# Power_Board_V1.net
KiCad netlist of a schematic drawn in EAGLE
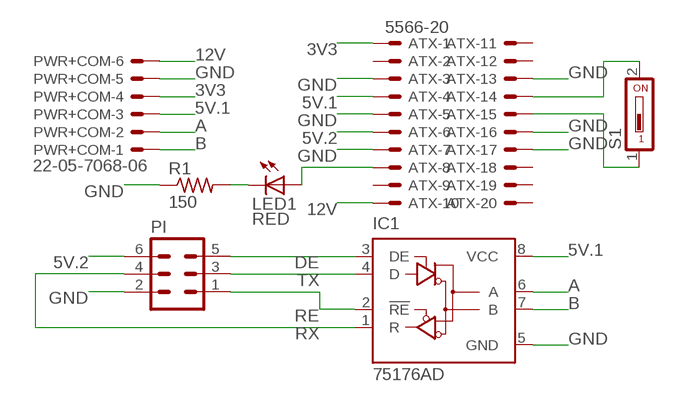
[diagram p0: schematic, sheet 1]

(export (version "E")
  (design (tool "Eeschema 10.0.6"))
  (components
    (comp (ref "ATX")
      (value "5566-20")
      (footprint "eagle-import:5566-20")
      (libsource (lib "eagle-import") (part "5566-20"))
    )
    (comp (ref "IC1")
      (value "75176AD")
      (footprint "eagle-import:D_R-PDSO-G8")
      (libsource (lib "eagle-import") (part "75176AD"))
    )
    (comp (ref "LED1")
      (value "RED")
      (footprint "eagle-import:CHIPLED_1206")
      (libsource (lib "eagle-import") (part "LEDCHIPLED_1206"))
    )
    (comp (ref "PI")
      (value "MA03-2")
      (footprint "eagle-import:MA03-2")
      (libsource (lib "eagle-import") (part "MA03-2"))
    )
    (comp (ref "PWR+COM")
      (value "22-05-7068-06")
      (footprint "eagle-import:7395-06")
      (libsource (lib "eagle-import") (part "22-?-0605-7068"))
    )
    (comp (ref "R1")
      (value "150")
      (footprint "eagle-import:R0805")
      (libsource (lib "eagle-import") (part "R-US_R0805"))
    )
    (comp (ref "S1")
      (value "SD4-01")
      (footprint "eagle-import:SD4-01")
      (libsource (lib "eagle-import") (part "SD4-01"))
    )
  )
  (nets
    (net (code "1") (name "/3V3") (class "Default")
      (node (ref "ATX") (pin "1") (pinfunction "S_1") (pintype "passive"))
      (node (ref "PWR+COM") (pin "4") (pinfunction "S_4") (pintype "passive"))
    )
    (net (code "2") (name "/5V.1") (class "Default")
      (node (ref "ATX") (pin "4") (pinfunction "S_4") (pintype "passive"))
      (node (ref "IC1") (pin "8") (pinfunction "VCC_8") (pintype "power_in"))
      (node (ref "PWR+COM") (pin "3") (pinfunction "S_3") (pintype "passive"))
    )
    (net (code "3") (name "/5V.2") (class "Default")
      (node (ref "ATX") (pin "6") (pinfunction "S_6") (pintype "passive"))
      (node (ref "PI") (pin "6") (pinfunction "6_6") (pintype "passive"))
    )
    (net (code "4") (name "/12V") (class "Default")
      (node (ref "ATX") (pin "10") (pinfunction "S_10") (pintype "passive"))
      (node (ref "PWR+COM") (pin "6") (pinfunction "S_6") (pintype "passive"))
    )
    (net (code "5") (name "/A") (class "Default")
      (node (ref "IC1") (pin "6") (pinfunction "A_6") (pintype "output"))
      (node (ref "PWR+COM") (pin "2") (pinfunction "S_2") (pintype "passive"))
    )
    (net (code "6") (name "/B") (class "Default")
      (node (ref "IC1") (pin "7") (pinfunction "B_7") (pintype "output"))
      (node (ref "PWR+COM") (pin "1") (pinfunction "S_1") (pintype "passive"))
    )
    (net (code "7") (name "/DE") (class "Default")
      (node (ref "IC1") (pin "3") (pinfunction "DE_3") (pintype "input"))
      (node (ref "PI") (pin "5") (pinfunction "5_5") (pintype "passive"))
    )
    (net (code "8") (name "/GND") (class "Default")
      (node (ref "ATX") (pin "13") (pinfunction "S_13") (pintype "passive"))
      (node (ref "ATX") (pin "16") (pinfunction "S_16") (pintype "passive"))
      (node (ref "ATX") (pin "17") (pinfunction "S_17") (pintype "passive"))
      (node (ref "ATX") (pin "3") (pinfunction "S_3") (pintype "passive"))
      (node (ref "ATX") (pin "5") (pinfunction "S_5") (pintype "passive"))
      (node (ref "ATX") (pin "7") (pinfunction "S_7") (pintype "passive"))
      (node (ref "IC1") (pin "5") (pinfunction "GND_5") (pintype "power_in"))
      (node (ref "PI") (pin "2") (pinfunction "2_2") (pintype "passive"))
      (node (ref "PWR+COM") (pin "5") (pinfunction "S_5") (pintype "passive"))
      (node (ref "R1") (pin "1") (pinfunction "1_1") (pintype "passive"))
    )
    (net (code "9") (name "/RE") (class "Default")
      (node (ref "IC1") (pin "2") (pinfunction "~{RE}_2") (pintype "input"))
      (node (ref "PI") (pin "1") (pinfunction "1_1") (pintype "passive"))
    )
    (net (code "10") (name "/RX") (class "Default")
      (node (ref "IC1") (pin "1") (pinfunction "R_1") (pintype "input"))
      (node (ref "PI") (pin "4") (pinfunction "4_4") (pintype "passive"))
    )
    (net (code "11") (name "/TX") (class "Default")
      (node (ref "IC1") (pin "4") (pinfunction "D_4") (pintype "input"))
      (node (ref "PI") (pin "3") (pinfunction "3_3") (pintype "passive"))
    )
    (net (code "12") (name "Net-(ATXF-S)") (class "Default")
      (node (ref "ATX") (pin "14") (pinfunction "S_14") (pintype "passive"))
      (node (ref "S1") (pin "2") (pinfunction "2_2") (pintype "passive"))
    )
    (net (code "13") (name "Net-(ATXG-S)") (class "Default")
      (node (ref "ATX") (pin "15") (pinfunction "S_15") (pintype "passive"))
      (node (ref "S1") (pin "1") (pinfunction "1_1") (pintype "passive"))
    )
    (net (code "14") (name "Net-(ATXS-S)") (class "Default")
      (node (ref "ATX") (pin "8") (pinfunction "S_8") (pintype "passive"))
      (node (ref "LED1") (pin "A") (pinfunction "A_A") (pintype "passive"))
    )
    (net (code "15") (name "Net-(LED1-PadC)") (class "Default")
      (node (ref "LED1") (pin "C") (pinfunction "C_C") (pintype "passive"))
      (node (ref "R1") (pin "2") (pinfunction "2_2") (pintype "passive"))
    )
    (net (code "16") (name "unconnected-(ATXC-S-Pad11)") (class "Default")
      (node (ref "ATX") (pin "11") (pinfunction "S_11") (pintype "passive"))
    )
    (net (code "17") (name "unconnected-(ATXD-S-Pad12)") (class "Default")
      (node (ref "ATX") (pin "12") (pinfunction "S_12") (pintype "passive"))
    )
    (net (code "18") (name "unconnected-(ATXJ-S-Pad18)") (class "Default")
      (node (ref "ATX") (pin "18") (pinfunction "S_18") (pintype "passive"))
    )
    (net (code "19") (name "unconnected-(ATXK-S-Pad19)") (class "Default")
      (node (ref "ATX") (pin "19") (pinfunction "S_19") (pintype "passive"))
    )
    (net (code "20") (name "unconnected-(ATXL-S-Pad2)") (class "Default")
      (node (ref "ATX") (pin "2") (pinfunction "S_2") (pintype "passive"))
    )
    (net (code "21") (name "unconnected-(ATXM-S-Pad20)") (class "Default")
      (node (ref "ATX") (pin "20") (pinfunction "S_20") (pintype "passive"))
    )
    (net (code "22") (name "unconnected-(ATXT-S-Pad9)") (class "Default")
      (node (ref "ATX") (pin "9") (pinfunction "S_9") (pintype "passive"))
    )
  )
)
